# alt-com.net
KiCad netlist of a schematic drawn in EAGLE
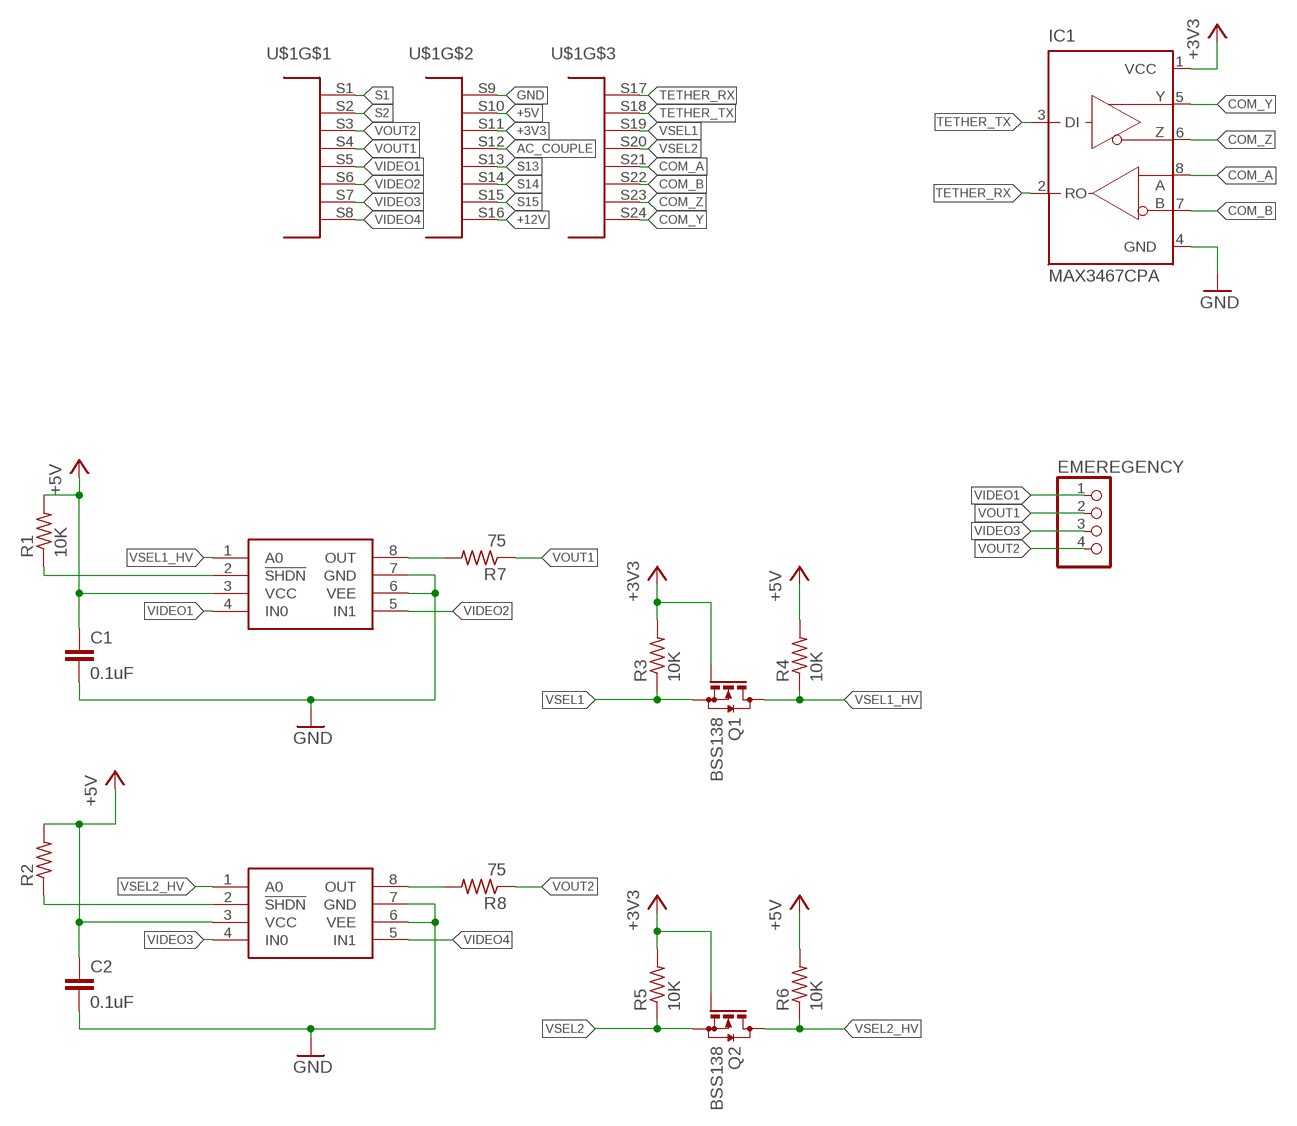
[diagram p0: schematic, sheet 1]

(export (version "E")
  (design (tool "Eeschema 10.0.6"))
  (components
    (comp (ref "C1")
      (value "0.1uF")
      (footprint "eagle-import:C0603")
      (libsource (lib "eagle-import") (part "C-EUC0603"))
    )
    (comp (ref "C2")
      (value "0.1uF")
      (footprint "eagle-import:C0603")
      (libsource (lib "eagle-import") (part "C-EUC0603"))
    )
    (comp (ref "EMEREGENCY")
      (value "PINHD-1X4")
      (footprint "eagle-import:1X04")
      (libsource (lib "eagle-import") (part "PINHD-1X4"))
    )
    (comp (ref "IC1")
      (value "MAX3467CPA")
      (footprint "eagle-import:SO08")
      (libsource (lib "eagle-import") (part "MAX3467PAC"))
    )
    (comp (ref "Q1")
      (value "BSS138")
      (footprint "eagle-import:SOT23")
      (libsource (lib "eagle-import") (part "BSS123"))
    )
    (comp (ref "Q2")
      (value "BSS138")
      (footprint "eagle-import:SOT23")
      (libsource (lib "eagle-import") (part "BSS123"))
    )
    (comp (ref "R1")
      (value "10K")
      (footprint "eagle-import:R0603")
      (libsource (lib "eagle-import") (part "R-US_R0603"))
    )
    (comp (ref "R2")
      (value "R-US_R0603")
      (footprint "eagle-import:R0603")
      (libsource (lib "eagle-import") (part "R-US_R0603"))
    )
    (comp (ref "R3")
      (value "10K")
      (footprint "eagle-import:R0603")
      (libsource (lib "eagle-import") (part "R-US_R0603"))
    )
    (comp (ref "R4")
      (value "10K")
      (footprint "eagle-import:R0603")
      (libsource (lib "eagle-import") (part "R-US_R0603"))
    )
    (comp (ref "R5")
      (value "10K")
      (footprint "eagle-import:R0603")
      (libsource (lib "eagle-import") (part "R-US_R0603"))
    )
    (comp (ref "R6")
      (value "10K")
      (footprint "eagle-import:R0603")
      (libsource (lib "eagle-import") (part "R-US_R0603"))
    )
    (comp (ref "R7")
      (value "75")
      (footprint "eagle-import:R0603")
      (libsource (lib "eagle-import") (part "R-US_R0603"))
    )
    (comp (ref "R8")
      (value "75")
      (footprint "eagle-import:R0603")
      (libsource (lib "eagle-import") (part "R-US_R0603"))
    )
    (comp (ref "U$1")
      (value "TEN60-S24-RA-2")
      (footprint "eagle-import:TEN60-S24-RA-2")
      (libsource (lib "eagle-import") (part "TEN60-S24-RA-2"))
    )
    (comp (ref "U$2")
      (value "MAX4313")
      (footprint "eagle-import:UMAX")
      (libsource (lib "eagle-import") (part "MAX4313"))
    )
    (comp (ref "U$3")
      (value "MAX4313")
      (footprint "eagle-import:UMAX")
      (libsource (lib "eagle-import") (part "MAX4313"))
    )
  )
  (nets
    (net (code "1") (name "+3V3") (class "Default")
      (node (ref "IC1") (pin "1") (pinfunction "VCC_1") (pintype "power_in"))
      (node (ref "Q1") (pin "1") (pinfunction "G_1") (pintype "passive"))
      (node (ref "Q2") (pin "1") (pinfunction "G_1") (pintype "passive"))
      (node (ref "R3") (pin "2") (pinfunction "2_2") (pintype "passive"))
      (node (ref "R5") (pin "2") (pinfunction "2_2") (pintype "passive"))
      (node (ref "U$1") (pin "S11") (pinfunction "P$3_S11") (pintype "bidirectional"))
    )
    (net (code "2") (name "+5V") (class "Default")
      (node (ref "C1") (pin "1") (pinfunction "1_1") (pintype "passive"))
      (node (ref "C2") (pin "1") (pinfunction "1_1") (pintype "passive"))
      (node (ref "R1") (pin "2") (pinfunction "2_2") (pintype "passive"))
      (node (ref "R2") (pin "2") (pinfunction "2_2") (pintype "passive"))
      (node (ref "R4") (pin "2") (pinfunction "2_2") (pintype "passive"))
      (node (ref "R6") (pin "2") (pinfunction "2_2") (pintype "passive"))
      (node (ref "U$1") (pin "S10") (pinfunction "P$2_S10") (pintype "bidirectional"))
      (node (ref "U$2") (pin "3") (pinfunction "VCC_3") (pintype "bidirectional"))
      (node (ref "U$3") (pin "3") (pinfunction "VCC_3") (pintype "bidirectional"))
    )
    (net (code "3") (name "+12V") (class "Default")
      (node (ref "U$1") (pin "S16") (pinfunction "P$8_S16") (pintype "bidirectional"))
    )
    (net (code "4") (name "AC_COUPLE") (class "Default")
      (node (ref "U$1") (pin "S12") (pinfunction "P$4_S12") (pintype "bidirectional"))
    )
    (net (code "5") (name "COM_A") (class "Default")
      (node (ref "IC1") (pin "8") (pinfunction "A_8") (pintype "passive"))
      (node (ref "U$1") (pin "S21") (pinfunction "P$5_S21") (pintype "bidirectional"))
    )
    (net (code "6") (name "COM_B") (class "Default")
      (node (ref "IC1") (pin "7") (pinfunction "B_7") (pintype "passive"))
      (node (ref "U$1") (pin "S22") (pinfunction "P$6_S22") (pintype "bidirectional"))
    )
    (net (code "7") (name "COM_Y") (class "Default")
      (node (ref "IC1") (pin "5") (pinfunction "Y_5") (pintype "passive"))
      (node (ref "U$1") (pin "S24") (pinfunction "P$8_S24") (pintype "bidirectional"))
    )
    (net (code "8") (name "COM_Z") (class "Default")
      (node (ref "IC1") (pin "6") (pinfunction "Z_6") (pintype "passive"))
      (node (ref "U$1") (pin "S23") (pinfunction "P$7_S23") (pintype "bidirectional"))
    )
    (net (code "9") (name "GND") (class "Default")
      (node (ref "C1") (pin "2") (pinfunction "2_2") (pintype "passive"))
      (node (ref "C2") (pin "2") (pinfunction "2_2") (pintype "passive"))
      (node (ref "IC1") (pin "4") (pinfunction "GND_4") (pintype "power_in"))
      (node (ref "U$1") (pin "S9") (pinfunction "P$1_S9") (pintype "bidirectional"))
      (node (ref "U$2") (pin "6") (pinfunction "VEE_6") (pintype "bidirectional"))
      (node (ref "U$2") (pin "7") (pinfunction "GND_7") (pintype "bidirectional"))
      (node (ref "U$3") (pin "6") (pinfunction "VEE_6") (pintype "bidirectional"))
      (node (ref "U$3") (pin "7") (pinfunction "GND_7") (pintype "bidirectional"))
    )
    (net (code "10") (name "Net-(U$2-OUT)") (class "Default")
      (node (ref "R7") (pin "2") (pinfunction "2_2") (pintype "passive"))
      (node (ref "U$2") (pin "8") (pinfunction "OUT_8") (pintype "bidirectional"))
    )
    (net (code "11") (name "Net-(U$2-~{SHDN})") (class "Default")
      (node (ref "R1") (pin "1") (pinfunction "1_1") (pintype "passive"))
      (node (ref "U$2") (pin "2") (pinfunction "~{SHDN}_2") (pintype "bidirectional"))
    )
    (net (code "12") (name "Net-(U$3-OUT)") (class "Default")
      (node (ref "R8") (pin "2") (pinfunction "2_2") (pintype "passive"))
      (node (ref "U$3") (pin "8") (pinfunction "OUT_8") (pintype "bidirectional"))
    )
    (net (code "13") (name "Net-(U$3-~{SHDN})") (class "Default")
      (node (ref "R2") (pin "1") (pinfunction "1_1") (pintype "passive"))
      (node (ref "U$3") (pin "2") (pinfunction "~{SHDN}_2") (pintype "bidirectional"))
    )
    (net (code "14") (name "S1") (class "Default")
      (node (ref "U$1") (pin "S1") (pinfunction "P$1_S1") (pintype "bidirectional"))
    )
    (net (code "15") (name "S2") (class "Default")
      (node (ref "U$1") (pin "S2") (pinfunction "P$2_S2") (pintype "bidirectional"))
    )
    (net (code "16") (name "S13") (class "Default")
      (node (ref "U$1") (pin "S13") (pinfunction "P$5_S13") (pintype "bidirectional"))
    )
    (net (code "17") (name "S14") (class "Default")
      (node (ref "U$1") (pin "S14") (pinfunction "P$6_S14") (pintype "bidirectional"))
    )
    (net (code "18") (name "S15") (class "Default")
      (node (ref "U$1") (pin "S15") (pinfunction "P$7_S15") (pintype "bidirectional"))
    )
    (net (code "19") (name "TETHER_RX") (class "Default")
      (node (ref "IC1") (pin "2") (pinfunction "RO_2") (pintype "output"))
      (node (ref "U$1") (pin "S17") (pinfunction "P$1_S17") (pintype "bidirectional"))
    )
    (net (code "20") (name "TETHER_TX") (class "Default")
      (node (ref "IC1") (pin "3") (pinfunction "DI_3") (pintype "input"))
      (node (ref "U$1") (pin "S18") (pinfunction "P$2_S18") (pintype "bidirectional"))
    )
    (net (code "21") (name "VIDEO1") (class "Default")
      (node (ref "EMEREGENCY") (pin "1") (pinfunction "1_1") (pintype "passive"))
      (node (ref "U$1") (pin "S5") (pinfunction "P$5_S5") (pintype "bidirectional"))
      (node (ref "U$2") (pin "4") (pinfunction "IN0_4") (pintype "bidirectional"))
    )
    (net (code "22") (name "VIDEO2") (class "Default")
      (node (ref "U$1") (pin "S6") (pinfunction "P$6_S6") (pintype "bidirectional"))
      (node (ref "U$2") (pin "5") (pinfunction "IN1_5") (pintype "bidirectional"))
    )
    (net (code "23") (name "VIDEO3") (class "Default")
      (node (ref "EMEREGENCY") (pin "3") (pinfunction "3_3") (pintype "passive"))
      (node (ref "U$1") (pin "S7") (pinfunction "P$7_S7") (pintype "bidirectional"))
      (node (ref "U$3") (pin "4") (pinfunction "IN0_4") (pintype "bidirectional"))
    )
    (net (code "24") (name "VIDEO4") (class "Default")
      (node (ref "U$1") (pin "S8") (pinfunction "P$8_S8") (pintype "bidirectional"))
      (node (ref "U$3") (pin "5") (pinfunction "IN1_5") (pintype "bidirectional"))
    )
    (net (code "25") (name "VOUT1") (class "Default")
      (node (ref "EMEREGENCY") (pin "2") (pinfunction "2_2") (pintype "passive"))
      (node (ref "R7") (pin "1") (pinfunction "1_1") (pintype "passive"))
      (node (ref "U$1") (pin "S4") (pinfunction "P$4_S4") (pintype "bidirectional"))
    )
    (net (code "26") (name "VOUT2") (class "Default")
      (node (ref "EMEREGENCY") (pin "4") (pinfunction "4_4") (pintype "passive"))
      (node (ref "R8") (pin "1") (pinfunction "1_1") (pintype "passive"))
      (node (ref "U$1") (pin "S3") (pinfunction "P$3_S3") (pintype "bidirectional"))
    )
    (net (code "27") (name "VSEL1") (class "Default")
      (node (ref "Q1") (pin "2") (pinfunction "S_2") (pintype "passive"))
      (node (ref "R3") (pin "1") (pinfunction "1_1") (pintype "passive"))
      (node (ref "U$1") (pin "S19") (pinfunction "P$3_S19") (pintype "bidirectional"))
    )
    (net (code "28") (name "VSEL1_HV") (class "Default")
      (node (ref "Q1") (pin "3") (pinfunction "D_3") (pintype "passive"))
      (node (ref "R4") (pin "1") (pinfunction "1_1") (pintype "passive"))
      (node (ref "U$2") (pin "1") (pinfunction "A0_1") (pintype "bidirectional"))
    )
    (net (code "29") (name "VSEL2") (class "Default")
      (node (ref "Q2") (pin "2") (pinfunction "S_2") (pintype "passive"))
      (node (ref "R5") (pin "1") (pinfunction "1_1") (pintype "passive"))
      (node (ref "U$1") (pin "S20") (pinfunction "P$4_S20") (pintype "bidirectional"))
    )
    (net (code "30") (name "VSEL2_HV") (class "Default")
      (node (ref "Q2") (pin "3") (pinfunction "D_3") (pintype "passive"))
      (node (ref "R6") (pin "1") (pinfunction "1_1") (pintype "passive"))
      (node (ref "U$3") (pin "1") (pinfunction "A0_1") (pintype "bidirectional"))
    )
  )
)
